# mapleCUx_large_340-007.net
KiCad netlist of a schematic drawn in EAGLE
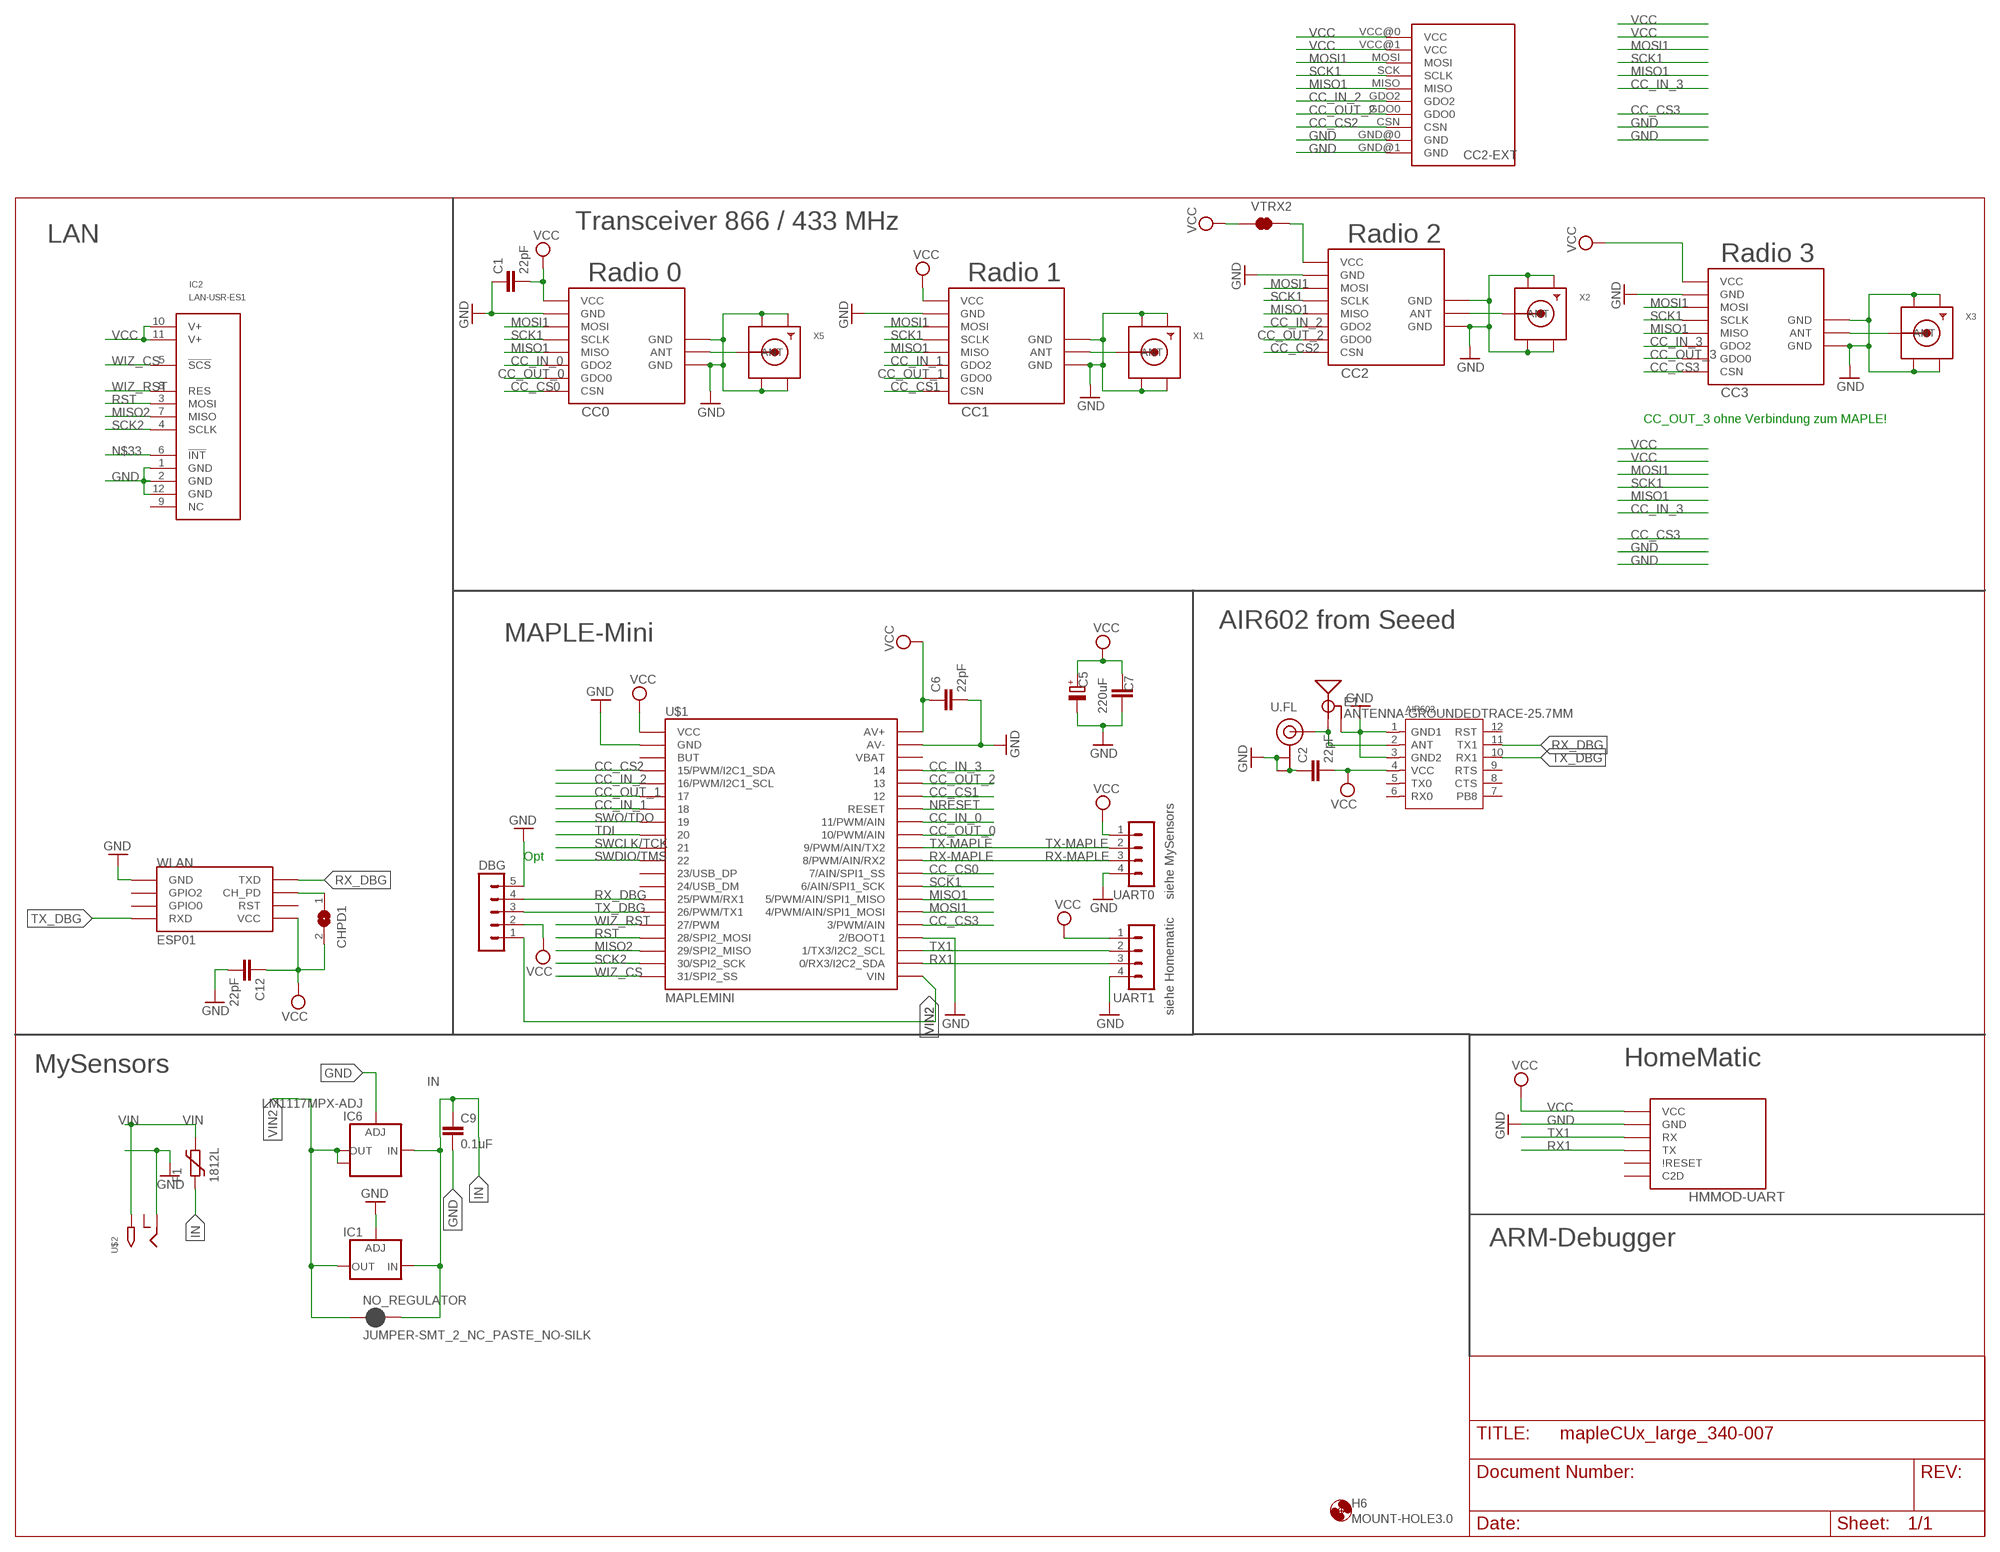
[diagram p0: schematic, sheet 1]

(export (version "E")
  (design (tool "Eeschema 10.0.6"))
  (components
    (comp (ref "AIR602")
      (value "AIR602")
      (footprint "eagle-import:MODULE12P-2.0-10X12MM")
      (libsource (lib "eagle-import") (part "AIR602"))
    )
    (comp (ref "C1")
      (value "22pF")
      (footprint "eagle-import:C0805")
      (libsource (lib "eagle-import") (part "C-EUC0805"))
    )
    (comp (ref "C2")
      (value "22pF")
      (footprint "eagle-import:C0805")
      (libsource (lib "eagle-import") (part "C-EUC0805"))
    )
    (comp (ref "C5")
      (value "220uF")
      (footprint "eagle-import:E5-8,5")
      (libsource (lib "eagle-import") (part "CPOL-EUE5-8.5"))
    )
    (comp (ref "C6")
      (value "22pF")
      (footprint "eagle-import:C0805")
      (libsource (lib "eagle-import") (part "C-EUC0805"))
    )
    (comp (ref "C7")
      (value "C-EUC1812")
      (footprint "eagle-import:C1812")
      (libsource (lib "eagle-import") (part "C-EUC1812"))
    )
    (comp (ref "C9")
      (value "0.1uF")
      (footprint "eagle-import:C1206")
      (libsource (lib "eagle-import") (part "C-EUC1206"))
    )
    (comp (ref "C12")
      (value "22pF")
      (footprint "eagle-import:C0805")
      (libsource (lib "eagle-import") (part "C-EUC0805"))
    )
    (comp (ref "CC0")
      (value "CC1101")
      (footprint "eagle-import:CC1101_MODULE1_SMD")
      (libsource (lib "eagle-import") (part "CC1101_MODULE1SMD"))
    )
    (comp (ref "CC1")
      (value "CC1101_MODULE1SMD")
      (footprint "eagle-import:CC1101_MODULE1_SMD")
      (libsource (lib "eagle-import") (part "CC1101_MODULE1SMD"))
    )
    (comp (ref "CC2")
      (value "CC1101_MODULE1SMD")
      (footprint "eagle-import:CC1101_MODULE1_SMD")
      (libsource (lib "eagle-import") (part "CC1101_MODULE1SMD"))
    )
    (comp (ref "CC2-EXT")
      (value "CC1101_MODULE3_DIL")
      (footprint "eagle-import:CC1101_MODULE3_DIL")
      (libsource (lib "eagle-import") (part "CC1101_MODULE3_DIL"))
    )
    (comp (ref "CC3")
      (value "CC1101_MODULE1SMD")
      (footprint "eagle-import:CC1101_MODULE1_SMD")
      (libsource (lib "eagle-import") (part "CC1101_MODULE1SMD"))
    )
    (comp (ref "CHPD1")
      (value "SJ")
      (footprint "eagle-import:SJ")
      (libsource (lib "eagle-import") (part "SJ"))
    )
    (comp (ref "DBG")
      (value "MA05-1")
      (footprint "eagle-import:MA05-1")
      (libsource (lib "eagle-import") (part "MA05-1"))
    )
    (comp (ref "E1")
      (value "ANTENNA-GROUNDEDTRACE-25.7MM")
      (footprint "eagle-import:TRACE_ANTENNA_2.4GHZ_25.7MM")
      (libsource (lib "eagle-import") (part "ANTENNA-GROUNDEDTRACE-25.7MM"))
    )
    (comp (ref "F1")
      (value "1812L")
      (footprint "eagle-import:1812L")
      (libsource (lib "eagle-import") (part "1812L"))
    )
    (comp (ref "H6")
      (value "MOUNT-HOLE3.0")
      (footprint "eagle-import:3,0")
      (libsource (lib "eagle-import") (part "MOUNT-HOLE3.0"))
    )
    (comp (ref "HMMOD-UART")
      (value "HM-MOD-UARTDIL")
      (footprint "eagle-import:HM-MOD-UART-DIL")
      (libsource (lib "eagle-import") (part "HM-MOD-UARTDIL"))
    )
    (comp (ref "IC1")
      (value "LD117ADT50TR")
      (footprint "eagle-import:DPACK")
      (libsource (lib "eagle-import") (part "LD117A?DT50TR"))
    )
    (comp (ref "IC2")
      (value "LAN-USR-ES1")
      (footprint "eagle-import:USR-ES1")
      (libsource (lib "eagle-import") (part "LAN-USR-ES1"))
    )
    (comp (ref "IC6")
      (value "LM1117MPX-ADJ")
      (footprint "eagle-import:SOT223")
      (libsource (lib "eagle-import") (part "LM1117MPX-ADJ"))
    )
    (comp (ref "NO_REGULATOR")
      (value "JUMPER-SMT_2_NC_PASTE_NO-SILK")
      (footprint "eagle-import:SMT-JUMPER_2_NC_PASTE_NO-SILK")
      (libsource (lib "eagle-import") (part "JUMPER-SMT_2_NC_PASTE_NO-SILK"))
    )
    (comp (ref "U$1")
      (value "MAPLEMINI")
      (footprint "eagle-import:20-DIP")
      (libsource (lib "eagle-import") (part "MAPLEMINI"))
    )
    (comp (ref "U$2")
      (value "2.1MMJACKTHM")
      (footprint "eagle-import:PJ-102A")
      (libsource (lib "eagle-import") (part "2.1MMJACKTHM"))
    )
    (comp (ref "U.FL")
      (value "U.FL")
      (footprint "eagle-import:U.FL")
      (libsource (lib "eagle-import") (part "U.FL"))
    )
    (comp (ref "UART0")
      (value "MA04-1")
      (footprint "eagle-import:MA04-1")
      (libsource (lib "eagle-import") (part "MA04-1"))
    )
    (comp (ref "UART1")
      (value "MA04-1")
      (footprint "eagle-import:MA04-1")
      (libsource (lib "eagle-import") (part "MA04-1"))
    )
    (comp (ref "VTRX2")
      (value "JUMPER-SMT_2_NC_TRACE_SILK")
      (footprint "eagle-import:SMT-JUMPER_2_NC_TRACE_SILK")
      (libsource (lib "eagle-import") (part "JUMPER-SMT_2_NC_TRACE_SILK"))
    )
    (comp (ref "WLAN")
      (value "ESP01")
      (footprint "eagle-import:ESP01")
      (libsource (lib "eagle-import") (part "ESP01"))
    )
    (comp (ref "X1")
      (value "SMACONNECTOR_EDGE")
      (footprint "eagle-import:SMA_EDGELAUNCH")
      (libsource (lib "eagle-import") (part "SMACONNECTOR_EDGE"))
    )
    (comp (ref "X2")
      (value "SMACONNECTOR_EDGE")
      (footprint "eagle-import:SMA_EDGELAUNCH")
      (libsource (lib "eagle-import") (part "SMACONNECTOR_EDGE"))
    )
    (comp (ref "X3")
      (value "SMACONNECTOR_EDGE")
      (footprint "eagle-import:SMA_EDGELAUNCH")
      (libsource (lib "eagle-import") (part "SMACONNECTOR_EDGE"))
    )
    (comp (ref "X5")
      (value "SMACONNECTOR_EDGE")
      (footprint "eagle-import:SMA_EDGELAUNCH")
      (libsource (lib "eagle-import") (part "SMACONNECTOR_EDGE"))
    )
  )
  (nets
    (net (code "1") (name "/CC_CS0") (class "Default")
      (node (ref "CC0") (pin "CSN") (pinfunction "CSN_CSN") (pintype "bidirectional"))
      (node (ref "U$1") (pin "29") (pinfunction "7/AIN/SPI1_SS_29") (pintype "bidirectional"))
    )
    (net (code "2") (name "/CC_CS1") (class "Default")
      (node (ref "CC1") (pin "CSN") (pinfunction "CSN_CSN") (pintype "bidirectional"))
      (node (ref "U$1") (pin "35") (pinfunction "12_35") (pintype "bidirectional"))
    )
    (net (code "3") (name "/CC_CS2") (class "Default")
      (node (ref "CC2") (pin "CSN") (pinfunction "CSN_CSN") (pintype "bidirectional"))
      (node (ref "CC2-EXT") (pin "CSN") (pinfunction "CSN_CSN") (pintype "bidirectional"))
      (node (ref "U$1") (pin "4") (pinfunction "15/PWM/I2C1_SDA_4") (pintype "bidirectional"))
    )
    (net (code "4") (name "/CC_CS3") (class "Default")
      (node (ref "CC3") (pin "CSN") (pinfunction "CSN_CSN") (pintype "bidirectional"))
      (node (ref "U$1") (pin "25") (pinfunction "3/PWM/AIN_25") (pintype "bidirectional"))
    )
    (net (code "5") (name "/CC_IN_0") (class "Default")
      (node (ref "CC0") (pin "GDO2") (pinfunction "GDO2_GDO2") (pintype "bidirectional"))
      (node (ref "U$1") (pin "33") (pinfunction "11/PWM/AIN_33") (pintype "bidirectional"))
    )
    (net (code "6") (name "/CC_IN_1") (class "Default")
      (node (ref "CC1") (pin "GDO2") (pinfunction "GDO2_GDO2") (pintype "bidirectional"))
      (node (ref "U$1") (pin "7") (pinfunction "18_7") (pintype "bidirectional"))
    )
    (net (code "7") (name "/CC_IN_2") (class "Default")
      (node (ref "CC2") (pin "GDO2") (pinfunction "GDO2_GDO2") (pintype "bidirectional"))
      (node (ref "CC2-EXT") (pin "GDO2") (pinfunction "GDO2_GDO2") (pintype "bidirectional"))
      (node (ref "U$1") (pin "5") (pinfunction "16/PWM/I2C1_SCL_5") (pintype "bidirectional"))
    )
    (net (code "8") (name "/CC_IN_3") (class "Default")
      (node (ref "CC3") (pin "GDO2") (pinfunction "GDO2_GDO2") (pintype "bidirectional"))
      (node (ref "U$1") (pin "37") (pinfunction "14_37") (pintype "bidirectional"))
    )
    (net (code "9") (name "/CC_OUT_0") (class "Default")
      (node (ref "CC0") (pin "GDO0") (pinfunction "GDO0_GDO0") (pintype "bidirectional"))
      (node (ref "U$1") (pin "32") (pinfunction "10/PWM/AIN_32") (pintype "bidirectional"))
    )
    (net (code "10") (name "/CC_OUT_1") (class "Default")
      (node (ref "CC1") (pin "GDO0") (pinfunction "GDO0_GDO0") (pintype "bidirectional"))
      (node (ref "U$1") (pin "6") (pinfunction "17_6") (pintype "bidirectional"))
    )
    (net (code "11") (name "/CC_OUT_2") (class "Default")
      (node (ref "CC2") (pin "GDO0") (pinfunction "GDO0_GDO0") (pintype "bidirectional"))
      (node (ref "CC2-EXT") (pin "GDO0") (pinfunction "GDO0_GDO0") (pintype "bidirectional"))
      (node (ref "U$1") (pin "36") (pinfunction "13_36") (pintype "bidirectional"))
    )
    (net (code "12") (name "/CC_OUT_3") (class "Default")
      (node (ref "CC3") (pin "GDO0") (pinfunction "GDO0_GDO0") (pintype "bidirectional"))
    )
    (net (code "13") (name "/MISO1") (class "Default")
      (node (ref "CC0") (pin "MISO") (pinfunction "MISO_MISO") (pintype "bidirectional"))
      (node (ref "CC1") (pin "MISO") (pinfunction "MISO_MISO") (pintype "bidirectional"))
      (node (ref "CC2") (pin "MISO") (pinfunction "MISO_MISO") (pintype "bidirectional"))
      (node (ref "CC2-EXT") (pin "MISO") (pinfunction "MISO_MISO") (pintype "bidirectional"))
      (node (ref "CC3") (pin "MISO") (pinfunction "MISO_MISO") (pintype "bidirectional"))
      (node (ref "U$1") (pin "27") (pinfunction "5/PWM/AIN/SPI1_MISO_27") (pintype "bidirectional"))
    )
    (net (code "14") (name "/MISO2") (class "Default")
      (node (ref "IC2") (pin "7") (pinfunction "MISO_7") (pintype "bidirectional"))
      (node (ref "U$1") (pin "18") (pinfunction "29/SPI2_MISO_18") (pintype "bidirectional"))
    )
    (net (code "15") (name "/MOSI1") (class "Default")
      (node (ref "CC0") (pin "MOSI") (pinfunction "MOSI_MOSI") (pintype "bidirectional"))
      (node (ref "CC1") (pin "MOSI") (pinfunction "MOSI_MOSI") (pintype "bidirectional"))
      (node (ref "CC2") (pin "MOSI") (pinfunction "MOSI_MOSI") (pintype "bidirectional"))
      (node (ref "CC2-EXT") (pin "MOSI") (pinfunction "MOSI_MOSI") (pintype "bidirectional"))
      (node (ref "CC3") (pin "MOSI") (pinfunction "MOSI_MOSI") (pintype "bidirectional"))
      (node (ref "U$1") (pin "26") (pinfunction "4/PWM/AIN/SPI1_MOSI_26") (pintype "bidirectional"))
    )
    (net (code "16") (name "/N$33") (class "Default")
      (node (ref "IC2") (pin "6") (pinfunction "~{INT}_6") (pintype "output"))
    )
    (net (code "17") (name "/NRESET") (class "Default")
      (node (ref "U$1") (pin "34") (pinfunction "RESET_34") (pintype "bidirectional"))
    )
    (net (code "18") (name "/RST") (class "Default")
      (node (ref "IC2") (pin "3") (pinfunction "MOSI_3") (pintype "bidirectional"))
      (node (ref "U$1") (pin "17") (pinfunction "28/SPI2_MOSI_17") (pintype "bidirectional"))
    )
    (net (code "19") (name "/RX-MAPLE") (class "Default")
      (node (ref "U$1") (pin "30") (pinfunction "8/PWM/AIN/RX2_30") (pintype "bidirectional"))
      (node (ref "UART0") (pin "3") (pinfunction "3_3") (pintype "passive"))
    )
    (net (code "20") (name "/RX1") (class "Default")
      (node (ref "HMMOD-UART") (pin "5") (pinfunction "TX_5") (pintype "bidirectional"))
      (node (ref "U$1") (pin "22") (pinfunction "0/RX3/I2C2_SDA_22") (pintype "bidirectional"))
      (node (ref "UART1") (pin "3") (pinfunction "3_3") (pintype "passive"))
    )
    (net (code "21") (name "/SCK1") (class "Default")
      (node (ref "CC0") (pin "SCLK") (pinfunction "SCLK_SCLK") (pintype "bidirectional"))
      (node (ref "CC1") (pin "SCLK") (pinfunction "SCLK_SCLK") (pintype "bidirectional"))
      (node (ref "CC2") (pin "SCLK") (pinfunction "SCLK_SCLK") (pintype "bidirectional"))
      (node (ref "CC2-EXT") (pin "SCK") (pinfunction "SCLK_SCK") (pintype "bidirectional"))
      (node (ref "CC3") (pin "SCLK") (pinfunction "SCLK_SCLK") (pintype "bidirectional"))
      (node (ref "U$1") (pin "28") (pinfunction "6/AIN/SPI1_SCK_28") (pintype "bidirectional"))
    )
    (net (code "22") (name "/SCK2") (class "Default")
      (node (ref "IC2") (pin "4") (pinfunction "SCLK_4") (pintype "input"))
      (node (ref "U$1") (pin "19") (pinfunction "30/SPI2_SCK_19") (pintype "bidirectional"))
    )
    (net (code "23") (name "/SWCLK{slash}TCK") (class "Default")
      (node (ref "U$1") (pin "10") (pinfunction "21_10") (pintype "bidirectional"))
    )
    (net (code "24") (name "/SWDIO{slash}TMS") (class "Default")
      (node (ref "U$1") (pin "11") (pinfunction "22_11") (pintype "bidirectional"))
    )
    (net (code "25") (name "/SWO{slash}TDO") (class "Default")
      (node (ref "U$1") (pin "8") (pinfunction "19_8") (pintype "bidirectional"))
    )
    (net (code "26") (name "/TDI") (class "Default")
      (node (ref "U$1") (pin "9") (pinfunction "20_9") (pintype "bidirectional"))
    )
    (net (code "27") (name "/TX-MAPLE") (class "Default")
      (node (ref "U$1") (pin "31") (pinfunction "9/PWM/AIN/TX2_31") (pintype "bidirectional"))
      (node (ref "UART0") (pin "2") (pinfunction "2_2") (pintype "passive"))
    )
    (net (code "28") (name "/TX1") (class "Default")
      (node (ref "HMMOD-UART") (pin "6") (pinfunction "RX_6") (pintype "bidirectional"))
      (node (ref "U$1") (pin "23") (pinfunction "1/TX3/I2C2_SCL_23") (pintype "bidirectional"))
      (node (ref "UART1") (pin "2") (pinfunction "2_2") (pintype "passive"))
    )
    (net (code "29") (name "/VIN") (class "Default")
      (node (ref "F1") (pin "P$2") (pinfunction "2_P$2") (pintype "passive"))
      (node (ref "U$2") (pin "TIP") (pinfunction "TIP_TIP") (pintype "bidirectional"))
    )
    (net (code "30") (name "/WIZ_CS") (class "Default")
      (node (ref "IC2") (pin "5") (pinfunction "~{SCS}_5") (pintype "input"))
      (node (ref "U$1") (pin "20") (pinfunction "31/SPI2_SS_20") (pintype "bidirectional"))
    )
    (net (code "31") (name "/WIZ_RST") (class "Default")
      (node (ref "IC2") (pin "8") (pinfunction "RES_8") (pintype "input"))
      (node (ref "U$1") (pin "16") (pinfunction "27/PWM_16") (pintype "bidirectional"))
    )
    (net (code "32") (name "GND") (class "Default")
      (node (ref "AIR602") (pin "1") (pinfunction "GND1_1") (pintype "bidirectional"))
      (node (ref "AIR602") (pin "3") (pinfunction "GND2_3") (pintype "bidirectional"))
      (node (ref "C1") (pin "1") (pinfunction "1_1") (pintype "passive"))
      (node (ref "C12") (pin "2") (pinfunction "2_2") (pintype "passive"))
      (node (ref "C5") (pin "-") (pinfunction "-_-") (pintype "passive"))
      (node (ref "C6") (pin "2") (pinfunction "2_2") (pintype "passive"))
      (node (ref "C7") (pin "1") (pinfunction "1_1") (pintype "passive"))
      (node (ref "C9") (pin "2") (pinfunction "2_2") (pintype "passive"))
      (node (ref "CC0") (pin "GND@0") (pinfunction "GND_GND@0") (pintype "power_in"))
      (node (ref "CC0") (pin "GND@1") (pinfunction "GND_GND@1") (pintype "power_in"))
      (node (ref "CC0") (pin "GND@2") (pinfunction "GND_GND@2") (pintype "power_in"))
      (node (ref "CC1") (pin "GND@0") (pinfunction "GND_GND@0") (pintype "power_in"))
      (node (ref "CC1") (pin "GND@1") (pinfunction "GND_GND@1") (pintype "power_in"))
      (node (ref "CC1") (pin "GND@2") (pinfunction "GND_GND@2") (pintype "power_in"))
      (node (ref "CC2") (pin "GND@0") (pinfunction "GND_GND@0") (pintype "power_in"))
      (node (ref "CC2") (pin "GND@1") (pinfunction "GND_GND@1") (pintype "power_in"))
      (node (ref "CC2") (pin "GND@2") (pinfunction "GND_GND@2") (pintype "power_in"))
      (node (ref "CC2-EXT") (pin "GND@0") (pinfunction "GND_GND@0") (pintype "power_in"))
      (node (ref "CC2-EXT") (pin "GND@1") (pinfunction "GND_GND@1") (pintype "power_in"))
      (node (ref "CC3") (pin "GND@0") (pinfunction "GND_GND@0") (pintype "power_in"))
      (node (ref "CC3") (pin "GND@1") (pinfunction "GND_GND@1") (pintype "power_in"))
      (node (ref "CC3") (pin "GND@2") (pinfunction "GND_GND@2") (pintype "power_in"))
      (node (ref "DBG") (pin "5") (pinfunction "5_5") (pintype "passive"))
      (node (ref "E1") (pin "GND") (pinfunction "GND_GND") (pintype "bidirectional"))
      (node (ref "E1") (pin "GND2") (pinfunction "GND_GND2") (pintype "bidirectional"))
      (node (ref "HMMOD-UART") (pin "2") (pinfunction "GND_2") (pintype "power_in"))
      (node (ref "IC1") (pin "1") (pinfunction "ADJ_1") (pintype "input"))
      (node (ref "IC2") (pin "1") (pinfunction "GND_1") (pintype "power_in"))
      (node (ref "IC2") (pin "12") (pinfunction "GND_12") (pintype "power_in"))
      (node (ref "IC2") (pin "2") (pinfunction "GND_2") (pintype "power_in"))
      (node (ref "IC6") (pin "1") (pinfunction "ADJ_1") (pintype "input"))
      (node (ref "U$1") (pin "2") (pinfunction "GND_2") (pintype "bidirectional"))
      (node (ref "U$1") (pin "24") (pinfunction "2/BOOT1_24") (pintype "bidirectional"))
      (node (ref "U$1") (pin "39") (pinfunction "AV-_39") (pintype "bidirectional"))
      (node (ref "U$2") (pin "RING") (pinfunction "RING_RING") (pintype "bidirectional"))
      (node (ref "U.FL") (pin "1") (pinfunction "GND_1") (pintype "bidirectional"))
      (node (ref "U.FL") (pin "2") (pinfunction "GND_2") (pintype "bidirectional"))
      (node (ref "UART0") (pin "4") (pinfunction "4_4") (pintype "passive"))
      (node (ref "UART1") (pin "4") (pinfunction "4_4") (pintype "passive"))
      (node (ref "WLAN") (pin "GND") (pinfunction "GND_GND") (pintype "bidirectional"))
      (node (ref "X1") (pin "GND@1") (pinfunction "GND4_GND@1") (pintype "power_in"))
      (node (ref "X1") (pin "GND@2") (pinfunction "GND3_GND@2") (pintype "power_in"))
      (node (ref "X1") (pin "GND@3") (pinfunction "GND2_GND@3") (pintype "power_in"))
      (node (ref "X1") (pin "GND@4") (pinfunction "GND1_GND@4") (pintype "power_in"))
      (node (ref "X2") (pin "GND@1") (pinfunction "GND4_GND@1") (pintype "power_in"))
      (node (ref "X2") (pin "GND@2") (pinfunction "GND3_GND@2") (pintype "power_in"))
      (node (ref "X2") (pin "GND@3") (pinfunction "GND2_GND@3") (pintype "power_in"))
      (node (ref "X2") (pin "GND@4") (pinfunction "GND1_GND@4") (pintype "power_in"))
      (node (ref "X3") (pin "GND@1") (pinfunction "GND4_GND@1") (pintype "power_in"))
      (node (ref "X3") (pin "GND@2") (pinfunction "GND3_GND@2") (pintype "power_in"))
      (node (ref "X3") (pin "GND@3") (pinfunction "GND2_GND@3") (pintype "power_in"))
      (node (ref "X3") (pin "GND@4") (pinfunction "GND1_GND@4") (pintype "power_in"))
      (node (ref "X5") (pin "GND@1") (pinfunction "GND4_GND@1") (pintype "power_in"))
      (node (ref "X5") (pin "GND@2") (pinfunction "GND3_GND@2") (pintype "power_in"))
      (node (ref "X5") (pin "GND@3") (pinfunction "GND2_GND@3") (pintype "power_in"))
      (node (ref "X5") (pin "GND@4") (pinfunction "GND1_GND@4") (pintype "power_in"))
    )
    (net (code "33") (name "IN") (class "Default")
      (node (ref "C9") (pin "1") (pinfunction "1_1") (pintype "passive"))
      (node (ref "F1") (pin "P$1") (pinfunction "1_P$1") (pintype "passive"))
      (node (ref "IC1") (pin "3") (pinfunction "IN_3") (pintype "input"))
      (node (ref "IC6") (pin "3") (pinfunction "IN_3") (pintype "input"))
      (node (ref "NO_REGULATOR") (pin "2") (pinfunction "2_2") (pintype "passive"))
    )
    (net (code "34") (name "Net-(AIR602-ANT)") (class "Default")
      (node (ref "AIR602") (pin "2") (pinfunction "ANT_2") (pintype "bidirectional"))
      (node (ref "E1") (pin "ANT") (pinfunction "SIGNAL_ANT") (pintype "bidirectional"))
      (node (ref "U.FL") (pin "FEED") (pinfunction "SIGNAL_FEED") (pintype "bidirectional"))
    )
    (net (code "35") (name "Net-(CC2-PadVCC)") (class "Default")
      (node (ref "CC2") (pin "VCC") (pinfunction "VCC_VCC") (pintype "power_in"))
      (node (ref "VTRX2") (pin "2") (pinfunction "2_2") (pintype "passive"))
    )
    (net (code "36") (name "Net-(CHPD1-Pad1)") (class "Default")
      (node (ref "CHPD1") (pin "1") (pinfunction "1_1") (pintype "passive"))
      (node (ref "WLAN") (pin "CH_PD") (pinfunction "CH_PD_CH_PD") (pintype "bidirectional"))
    )
    (net (code "37") (name "Net-(X1-ANT)") (class "Default")
      (node (ref "CC1") (pin "ANT") (pinfunction "ANT_ANT") (pintype "output"))
      (node (ref "X1") (pin "P") (pinfunction "ANT_P") (pintype "bidirectional"))
    )
    (net (code "38") (name "Net-(X2-ANT)") (class "Default")
      (node (ref "CC2") (pin "ANT") (pinfunction "ANT_ANT") (pintype "output"))
      (node (ref "X2") (pin "P") (pinfunction "ANT_P") (pintype "bidirectional"))
    )
    (net (code "39") (name "Net-(X3-ANT)") (class "Default")
      (node (ref "CC3") (pin "ANT") (pinfunction "ANT_ANT") (pintype "output"))
      (node (ref "X3") (pin "P") (pinfunction "ANT_P") (pintype "bidirectional"))
    )
    (net (code "40") (name "Net-(X5-ANT)") (class "Default")
      (node (ref "CC0") (pin "ANT") (pinfunction "ANT_ANT") (pintype "output"))
      (node (ref "X5") (pin "P") (pinfunction "ANT_P") (pintype "bidirectional"))
    )
    (net (code "41") (name "RX_DBG") (class "Default")
      (node (ref "AIR602") (pin "11") (pinfunction "TX1_11") (pintype "bidirectional"))
      (node (ref "DBG") (pin "4") (pinfunction "4_4") (pintype "passive"))
      (node (ref "U$1") (pin "14") (pinfunction "25/PWM/RX1_14") (pintype "bidirectional"))
      (node (ref "WLAN") (pin "TX") (pinfunction "TXD_TX") (pintype "bidirectional"))
    )
    (net (code "42") (name "TX_DBG") (class "Default")
      (node (ref "AIR602") (pin "10") (pinfunction "RX1_10") (pintype "bidirectional"))
      (node (ref "DBG") (pin "3") (pinfunction "3_3") (pintype "passive"))
      (node (ref "U$1") (pin "15") (pinfunction "26/PWM/TX1_15") (pintype "bidirectional"))
      (node (ref "WLAN") (pin "RX") (pinfunction "RXD_RX") (pintype "bidirectional"))
    )
    (net (code "43") (name "VCC") (class "Default")
      (node (ref "AIR602") (pin "4") (pinfunction "VCC_4") (pintype "bidirectional"))
      (node (ref "C1") (pin "2") (pinfunction "2_2") (pintype "passive"))
      (node (ref "C12") (pin "1") (pinfunction "1_1") (pintype "passive"))
      (node (ref "C2") (pin "2") (pinfunction "2_2") (pintype "passive"))
      (node (ref "C5") (pin "+") (pinfunction "+_+") (pintype "passive"))
      (node (ref "C6") (pin "1") (pinfunction "1_1") (pintype "passive"))
      (node (ref "C7") (pin "2") (pinfunction "2_2") (pintype "passive"))
      (node (ref "CC0") (pin "VCC") (pinfunction "VCC_VCC") (pintype "power_in"))
      (node (ref "CC1") (pin "VCC") (pinfunction "VCC_VCC") (pintype "power_in"))
      (node (ref "CC2-EXT") (pin "VCC@0") (pinfunction "VCC_VCC@0") (pintype "power_in"))
      (node (ref "CC2-EXT") (pin "VCC@1") (pinfunction "VCC_VCC@1") (pintype "power_in"))
      (node (ref "CC3") (pin "VCC") (pinfunction "VCC_VCC") (pintype "power_in"))
      (node (ref "CHPD1") (pin "2") (pinfunction "2_2") (pintype "passive"))
      (node (ref "DBG") (pin "2") (pinfunction "2_2") (pintype "passive"))
      (node (ref "HMMOD-UART") (pin "1") (pinfunction "VCC_1") (pintype "power_in"))
      (node (ref "IC2") (pin "10") (pinfunction "V+_10") (pintype "power_in"))
      (node (ref "IC2") (pin "11") (pinfunction "V+_11") (pintype "power_in"))
      (node (ref "U$1") (pin "1") (pinfunction "VCC_1") (pintype "bidirectional"))
      (node (ref "U$1") (pin "40") (pinfunction "AV+_40") (pintype "bidirectional"))
      (node (ref "UART0") (pin "1") (pinfunction "1_1") (pintype "passive"))
      (node (ref "UART1") (pin "1") (pinfunction "1_1") (pintype "passive"))
      (node (ref "VTRX2") (pin "1") (pinfunction "1_1") (pintype "passive"))
      (node (ref "WLAN") (pin "VCC") (pinfunction "VCC_VCC") (pintype "bidirectional"))
    )
    (net (code "44") (name "VIN2") (class "Default")
      (node (ref "DBG") (pin "1") (pinfunction "1_1") (pintype "passive"))
      (node (ref "IC1") (pin "4") (pinfunction "OUT_4") (pintype "passive"))
      (node (ref "IC6") (pin "2") (pinfunction "OUT_2") (pintype "passive"))
      (node (ref "IC6") (pin "TAB") (pinfunction "OUT1_TAB") (pintype "passive"))
      (node (ref "NO_REGULATOR") (pin "1") (pinfunction "1_1") (pintype "passive"))
      (node (ref "U$1") (pin "21") (pinfunction "VIN_21") (pintype "bidirectional"))
    )
    (net (code "45") (name "unconnected-(AIR602-CTS-Pad8)") (class "Default")
      (node (ref "AIR602") (pin "8") (pinfunction "CTS_8") (pintype "bidirectional"))
    )
    (net (code "46") (name "unconnected-(AIR602-PB8-Pad7)") (class "Default")
      (node (ref "AIR602") (pin "7") (pinfunction "PB8_7") (pintype "bidirectional"))
    )
    (net (code "47") (name "unconnected-(AIR602-RST-Pad12)") (class "Default")
      (node (ref "AIR602") (pin "12") (pinfunction "RST_12") (pintype "bidirectional"))
    )
    (net (code "48") (name "unconnected-(AIR602-RTS-Pad9)") (class "Default")
      (node (ref "AIR602") (pin "9") (pinfunction "RTS_9") (pintype "bidirectional"))
    )
    (net (code "49") (name "unconnected-(AIR602-RX0-Pad6)") (class "Default")
      (node (ref "AIR602") (pin "6") (pinfunction "RX0_6") (pintype "bidirectional"))
    )
    (net (code "50") (name "unconnected-(AIR602-TX0-Pad5)") (class "Default")
      (node (ref "AIR602") (pin "5") (pinfunction "TX0_5") (pintype "bidirectional"))
    )
    (net (code "51") (name "unconnected-(C2-Pad1)") (class "Default")
      (node (ref "C2") (pin "1") (pinfunction "1_1") (pintype "passive"))
    )
    (net (code "52") (name "unconnected-(HMMOD-UART-C2D-Pad3)") (class "Default")
      (node (ref "HMMOD-UART") (pin "3") (pinfunction "C2D_3") (pintype "bidirectional"))
    )
    (net (code "53") (name "unconnected-(HMMOD-UART-\\~{RESET}-Pad4)") (class "Default")
      (node (ref "HMMOD-UART") (pin "4") (pinfunction "\\~{RESET}_4") (pintype "bidirectional"))
    )
    (net (code "54") (name "unconnected-(IC2-NC-Pad9)") (class "Default")
      (node (ref "IC2") (pin "9") (pinfunction "NC_9") (pintype "no_connect"))
    )
    (net (code "55") (name "unconnected-(U$1-23{slash}USB_DP-Pad12)") (class "Default")
      (node (ref "U$1") (pin "12") (pinfunction "23/USB_DP_12") (pintype "bidirectional"))
    )
    (net (code "56") (name "unconnected-(U$1-24{slash}USB_DM-Pad13)") (class "Default")
      (node (ref "U$1") (pin "13") (pinfunction "24/USB_DM_13") (pintype "bidirectional"))
    )
    (net (code "57") (name "unconnected-(U$1-BUT-Pad3)") (class "Default")
      (node (ref "U$1") (pin "3") (pinfunction "BUT_3") (pintype "bidirectional"))
    )
    (net (code "58") (name "unconnected-(U$1-VBAT-Pad38)") (class "Default")
      (node (ref "U$1") (pin "38") (pinfunction "VBAT_38") (pintype "bidirectional"))
    )
    (net (code "59") (name "unconnected-(U$2-PadRING_SW)") (class "Default")
      (node (ref "U$2") (pin "RING_SW") (pinfunction "RING_SW_RING_SW") (pintype "bidirectional"))
    )
    (net (code "60") (name "unconnected-(WLAN-PadGPIO0)") (class "Default")
      (node (ref "WLAN") (pin "GPIO0") (pinfunction "GPIO0_GPIO0") (pintype "bidirectional"))
    )
    (net (code "61") (name "unconnected-(WLAN-PadGPIO2)") (class "Default")
      (node (ref "WLAN") (pin "GPIO2") (pinfunction "GPIO2_GPIO2") (pintype "bidirectional"))
    )
    (net (code "62") (name "unconnected-(WLAN-PadRST)") (class "Default")
      (node (ref "WLAN") (pin "RST") (pinfunction "RST_RST") (pintype "bidirectional"))
    )
  )
)
